# ui_board.net
KiCad netlist of a schematic drawn in EAGLE
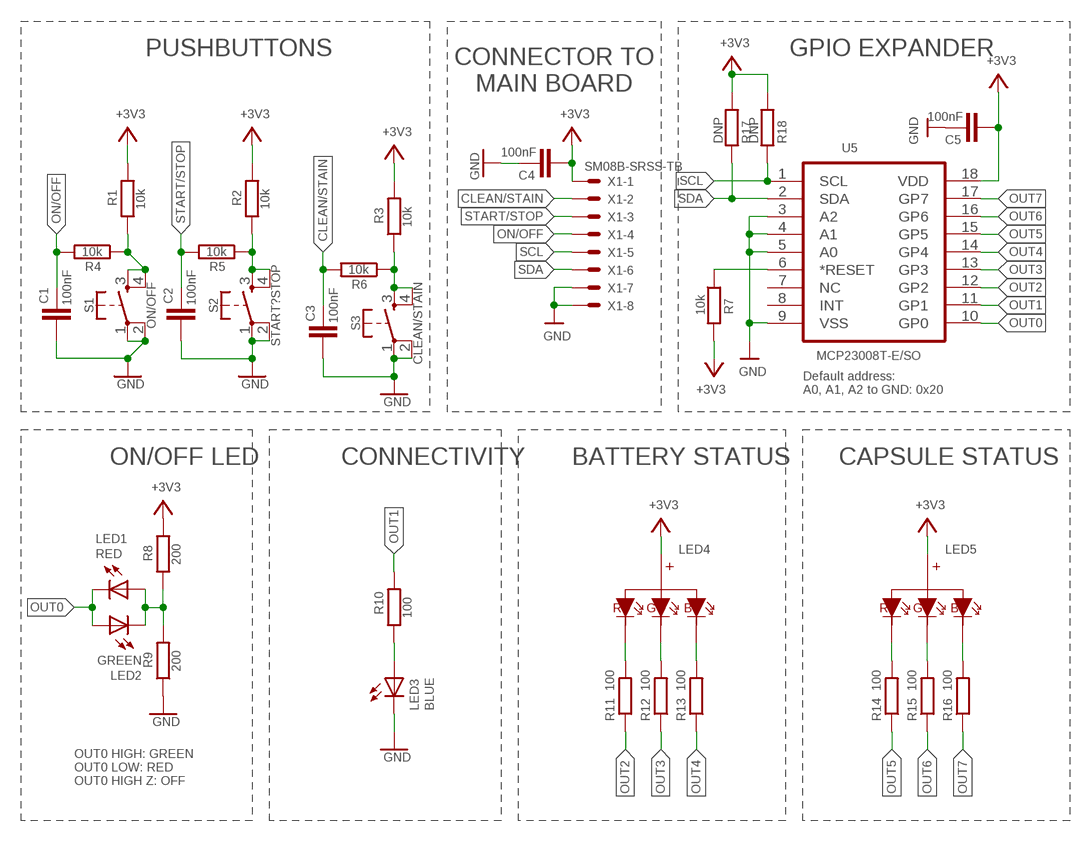
[diagram p0: schematic, sheet 1]

(export (version "E")
  (design (tool "Eeschema 10.0.6"))
  (components
    (comp (ref "C1")
      (value "100nF")
      (footprint "eagle-import:C0402")
      (libsource (lib "eagle-import") (part "C-EUC0402"))
    )
    (comp (ref "C2")
      (value "100nF")
      (footprint "eagle-import:C0402")
      (libsource (lib "eagle-import") (part "C-EUC0402"))
    )
    (comp (ref "C3")
      (value "100nF")
      (footprint "eagle-import:C0402")
      (libsource (lib "eagle-import") (part "C-EUC0402"))
    )
    (comp (ref "C4")
      (value "100nF")
      (footprint "eagle-import:C0402")
      (libsource (lib "eagle-import") (part "C-EUC0402"))
    )
    (comp (ref "C5")
      (value "100nF")
      (footprint "eagle-import:C0402")
      (libsource (lib "eagle-import") (part "C-EUC0402"))
    )
    (comp (ref "LED1")
      (value "RED")
      (footprint "eagle-import:CHIP-LED0603")
      (libsource (lib "eagle-import") (part "LEDCHIP-LED0603"))
    )
    (comp (ref "LED2")
      (value "GREEN")
      (footprint "eagle-import:CHIP-LED0603")
      (libsource (lib "eagle-import") (part "LEDCHIP-LED0603"))
    )
    (comp (ref "LED3")
      (value "BLUE")
      (footprint "eagle-import:CHIP-LED0603")
      (libsource (lib "eagle-import") (part "LEDCHIP-LED0603"))
    )
    (comp (ref "LED4")
      (value "RGB_CAV1")
      (footprint "eagle-import:19-037A_RSGHBHW")
      (libsource (lib "eagle-import") (part "RGB_CAV1"))
    )
    (comp (ref "LED5")
      (value "RGB_CAV1")
      (footprint "eagle-import:19-037A_RSGHBHW")
      (libsource (lib "eagle-import") (part "RGB_CAV1"))
    )
    (comp (ref "R1")
      (value "10k")
      (footprint "eagle-import:R0402")
      (libsource (lib "eagle-import") (part "R-EU_R0402"))
    )
    (comp (ref "R2")
      (value "10k")
      (footprint "eagle-import:R0402")
      (libsource (lib "eagle-import") (part "R-EU_R0402"))
    )
    (comp (ref "R3")
      (value "10k")
      (footprint "eagle-import:R0402")
      (libsource (lib "eagle-import") (part "R-EU_R0402"))
    )
    (comp (ref "R4")
      (value "10k")
      (footprint "eagle-import:R0402")
      (libsource (lib "eagle-import") (part "R-EU_R0402"))
    )
    (comp (ref "R5")
      (value "10k")
      (footprint "eagle-import:R0402")
      (libsource (lib "eagle-import") (part "R-EU_R0402"))
    )
    (comp (ref "R6")
      (value "10k")
      (footprint "eagle-import:R0402")
      (libsource (lib "eagle-import") (part "R-EU_R0402"))
    )
    (comp (ref "R7")
      (value "10k")
      (footprint "eagle-import:R0402")
      (libsource (lib "eagle-import") (part "R-EU_R0402"))
    )
    (comp (ref "R8")
      (value "200")
      (footprint "eagle-import:R0402")
      (libsource (lib "eagle-import") (part "R-EU_R0402"))
    )
    (comp (ref "R9")
      (value "200")
      (footprint "eagle-import:R0402")
      (libsource (lib "eagle-import") (part "R-EU_R0402"))
    )
    (comp (ref "R10")
      (value "100")
      (footprint "eagle-import:R0402")
      (libsource (lib "eagle-import") (part "R-EU_R0402"))
    )
    (comp (ref "R11")
      (value "100")
      (footprint "eagle-import:R0402")
      (libsource (lib "eagle-import") (part "R-EU_R0402"))
    )
    (comp (ref "R12")
      (value "100")
      (footprint "eagle-import:R0402")
      (libsource (lib "eagle-import") (part "R-EU_R0402"))
    )
    (comp (ref "R13")
      (value "100")
      (footprint "eagle-import:R0402")
      (libsource (lib "eagle-import") (part "R-EU_R0402"))
    )
    (comp (ref "R14")
      (value "100")
      (footprint "eagle-import:R0402")
      (libsource (lib "eagle-import") (part "R-EU_R0402"))
    )
    (comp (ref "R15")
      (value "100")
      (footprint "eagle-import:R0402")
      (libsource (lib "eagle-import") (part "R-EU_R0402"))
    )
    (comp (ref "R16")
      (value "100")
      (footprint "eagle-import:R0402")
      (libsource (lib "eagle-import") (part "R-EU_R0402"))
    )
    (comp (ref "R17")
      (value "DNP")
      (footprint "eagle-import:R0402")
      (libsource (lib "eagle-import") (part "R-EU_R0402"))
    )
    (comp (ref "R18")
      (value "DNP")
      (footprint "eagle-import:R0402")
      (libsource (lib "eagle-import") (part "R-EU_R0402"))
    )
    (comp (ref "S1")
      (value "ON/OFF")
      (footprint "eagle-import:TACTILE_SWITCH_SMD_5.2MM")
      (libsource (lib "eagle-import") (part "MOMENTARY-SWITCH-SPST-2-SMD-5.2MM"))
    )
    (comp (ref "S2")
      (value "START?STOP")
      (footprint "eagle-import:TACTILE_SWITCH_SMD_5.2MM")
      (libsource (lib "eagle-import") (part "MOMENTARY-SWITCH-SPST-2-SMD-5.2MM"))
    )
    (comp (ref "S3")
      (value "CLEAN/STAIN")
      (footprint "eagle-import:TACTILE_SWITCH_SMD_5.2MM")
      (libsource (lib "eagle-import") (part "MOMENTARY-SWITCH-SPST-2-SMD-5.2MM"))
    )
    (comp (ref "U5")
      (value "MCP23008T-E/SO")
      (footprint "eagle-import:SOIC127P1030X265-18N")
      (fields (field (name "MF") "Microchip"))
      (libsource (lib "eagle-import") (part "MCP23008T-E/SO"))
    )
    (comp (ref "X1")
      (value "SM08B-SRSS-TB")
      (footprint "eagle-import:SM08B-SRSS-TB")
      (libsource (lib "eagle-import") (part "?M08B-SRSS-TBS"))
    )
  )
  (nets
    (net (code "1") (name "+3V3") (class "Default")
      (node (ref "C4") (pin "2") (pinfunction "2_2") (pintype "passive"))
      (node (ref "C5") (pin "2") (pinfunction "2_2") (pintype "passive"))
      (node (ref "LED4") (pin "A") (pinfunction "A_A") (pintype "bidirectional"))
      (node (ref "LED5") (pin "A") (pinfunction "A_A") (pintype "bidirectional"))
      (node (ref "R1") (pin "2") (pinfunction "2_2") (pintype "passive"))
      (node (ref "R17") (pin "1") (pinfunction "1_1") (pintype "passive"))
      (node (ref "R18") (pin "1") (pinfunction "1_1") (pintype "passive"))
      (node (ref "R2") (pin "2") (pinfunction "2_2") (pintype "passive"))
      (node (ref "R3") (pin "2") (pinfunction "2_2") (pintype "passive"))
      (node (ref "R7") (pin "2") (pinfunction "2_2") (pintype "passive"))
      (node (ref "R8") (pin "2") (pinfunction "2_2") (pintype "passive"))
      (node (ref "U5") (pin "18") (pinfunction "VDD_18") (pintype "power_in"))
      (node (ref "X1") (pin "1") (pinfunction "S_1") (pintype "passive"))
    )
    (net (code "2") (name "CLEAN{slash}STAIN") (class "Default")
      (node (ref "C3") (pin "1") (pinfunction "1_1") (pintype "passive"))
      (node (ref "R6") (pin "2") (pinfunction "2_2") (pintype "passive"))
      (node (ref "X1") (pin "2") (pinfunction "S_2") (pintype "passive"))
    )
    (net (code "3") (name "GND") (class "Default")
      (node (ref "C1") (pin "2") (pinfunction "2_2") (pintype "passive"))
      (node (ref "C2") (pin "2") (pinfunction "2_2") (pintype "passive"))
      (node (ref "C3") (pin "2") (pinfunction "2_2") (pintype "passive"))
      (node (ref "C4") (pin "1") (pinfunction "1_1") (pintype "passive"))
      (node (ref "C5") (pin "1") (pinfunction "1_1") (pintype "passive"))
      (node (ref "LED3") (pin "C") (pinfunction "C_C") (pintype "passive"))
      (node (ref "R9") (pin "1") (pinfunction "1_1") (pintype "passive"))
      (node (ref "S1") (pin "1") (pinfunction "1_1") (pintype "passive"))
      (node (ref "S1") (pin "2") (pinfunction "2_2") (pintype "passive"))
      (node (ref "S2") (pin "1") (pinfunction "1_1") (pintype "passive"))
      (node (ref "S2") (pin "2") (pinfunction "2_2") (pintype "passive"))
      (node (ref "S3") (pin "1") (pinfunction "1_1") (pintype "passive"))
      (node (ref "S3") (pin "2") (pinfunction "2_2") (pintype "passive"))
      (node (ref "U5") (pin "3") (pinfunction "A2_3") (pintype "passive"))
      (node (ref "U5") (pin "4") (pinfunction "A1_4") (pintype "input"))
      (node (ref "U5") (pin "5") (pinfunction "A0_5") (pintype "input"))
      (node (ref "U5") (pin "9") (pinfunction "VSS_9") (pintype "passive"))
      (node (ref "X1") (pin "7") (pinfunction "S_7") (pintype "passive"))
      (node (ref "X1") (pin "8") (pinfunction "S_8") (pintype "passive"))
    )
    (net (code "4") (name "Net-(LED1-PadA)") (class "Default")
      (node (ref "LED1") (pin "A") (pinfunction "A_A") (pintype "passive"))
      (node (ref "LED2") (pin "C") (pinfunction "C_C") (pintype "passive"))
      (node (ref "R8") (pin "1") (pinfunction "1_1") (pintype "passive"))
      (node (ref "R9") (pin "2") (pinfunction "2_2") (pintype "passive"))
    )
    (net (code "5") (name "Net-(LED3-PadA)") (class "Default")
      (node (ref "LED3") (pin "A") (pinfunction "A_A") (pintype "passive"))
      (node (ref "R10") (pin "1") (pinfunction "1_1") (pintype "passive"))
    )
    (net (code "6") (name "Net-(LED4-PadB)") (class "Default")
      (node (ref "LED4") (pin "B") (pinfunction "B_B") (pintype "bidirectional"))
      (node (ref "R13") (pin "2") (pinfunction "2_2") (pintype "passive"))
    )
    (net (code "7") (name "Net-(LED4-PadG)") (class "Default")
      (node (ref "LED4") (pin "G") (pinfunction "G_G") (pintype "bidirectional"))
      (node (ref "R12") (pin "2") (pinfunction "2_2") (pintype "passive"))
    )
    (net (code "8") (name "Net-(LED4-PadR)") (class "Default")
      (node (ref "LED4") (pin "R") (pinfunction "R_R") (pintype "bidirectional"))
      (node (ref "R11") (pin "2") (pinfunction "2_2") (pintype "passive"))
    )
    (net (code "9") (name "Net-(LED5-PadB)") (class "Default")
      (node (ref "LED5") (pin "B") (pinfunction "B_B") (pintype "bidirectional"))
      (node (ref "R16") (pin "2") (pinfunction "2_2") (pintype "passive"))
    )
    (net (code "10") (name "Net-(LED5-PadG)") (class "Default")
      (node (ref "LED5") (pin "G") (pinfunction "G_G") (pintype "bidirectional"))
      (node (ref "R15") (pin "2") (pinfunction "2_2") (pintype "passive"))
    )
    (net (code "11") (name "Net-(LED5-PadR)") (class "Default")
      (node (ref "LED5") (pin "R") (pinfunction "R_R") (pintype "bidirectional"))
      (node (ref "R14") (pin "2") (pinfunction "2_2") (pintype "passive"))
    )
    (net (code "12") (name "Net-(R1-Pad1)") (class "Default")
      (node (ref "R1") (pin "1") (pinfunction "1_1") (pintype "passive"))
      (node (ref "R4") (pin "1") (pinfunction "1_1") (pintype "passive"))
      (node (ref "S1") (pin "3") (pinfunction "3_3") (pintype "passive"))
      (node (ref "S1") (pin "4") (pinfunction "4_4") (pintype "passive"))
    )
    (net (code "13") (name "Net-(R2-Pad1)") (class "Default")
      (node (ref "R2") (pin "1") (pinfunction "1_1") (pintype "passive"))
      (node (ref "R5") (pin "1") (pinfunction "1_1") (pintype "passive"))
      (node (ref "S2") (pin "3") (pinfunction "3_3") (pintype "passive"))
      (node (ref "S2") (pin "4") (pinfunction "4_4") (pintype "passive"))
    )
    (net (code "14") (name "Net-(R3-Pad1)") (class "Default")
      (node (ref "R3") (pin "1") (pinfunction "1_1") (pintype "passive"))
      (node (ref "R6") (pin "1") (pinfunction "1_1") (pintype "passive"))
      (node (ref "S3") (pin "3") (pinfunction "3_3") (pintype "passive"))
      (node (ref "S3") (pin "4") (pinfunction "4_4") (pintype "passive"))
    )
    (net (code "15") (name "Net-(U5-*RESET)") (class "Default")
      (node (ref "R7") (pin "1") (pinfunction "1_1") (pintype "passive"))
      (node (ref "U5") (pin "6") (pinfunction "*RESET_6") (pintype "input"))
    )
    (net (code "16") (name "ON{slash}OFF") (class "Default")
      (node (ref "C1") (pin "1") (pinfunction "1_1") (pintype "passive"))
      (node (ref "R4") (pin "2") (pinfunction "2_2") (pintype "passive"))
      (node (ref "X1") (pin "4") (pinfunction "S_4") (pintype "passive"))
    )
    (net (code "17") (name "OUT0") (class "Default")
      (node (ref "LED1") (pin "C") (pinfunction "C_C") (pintype "passive"))
      (node (ref "LED2") (pin "A") (pinfunction "A_A") (pintype "passive"))
      (node (ref "U5") (pin "10") (pinfunction "GP0_10") (pintype "passive"))
    )
    (net (code "18") (name "OUT1") (class "Default")
      (node (ref "R10") (pin "2") (pinfunction "2_2") (pintype "passive"))
      (node (ref "U5") (pin "11") (pinfunction "GP1_11") (pintype "passive"))
    )
    (net (code "19") (name "OUT2") (class "Default")
      (node (ref "R11") (pin "1") (pinfunction "1_1") (pintype "passive"))
      (node (ref "U5") (pin "12") (pinfunction "GP2_12") (pintype "passive"))
    )
    (net (code "20") (name "OUT3") (class "Default")
      (node (ref "R12") (pin "1") (pinfunction "1_1") (pintype "passive"))
      (node (ref "U5") (pin "13") (pinfunction "GP3_13") (pintype "passive"))
    )
    (net (code "21") (name "OUT4") (class "Default")
      (node (ref "R13") (pin "1") (pinfunction "1_1") (pintype "passive"))
      (node (ref "U5") (pin "14") (pinfunction "GP4_14") (pintype "passive"))
    )
    (net (code "22") (name "OUT5") (class "Default")
      (node (ref "R14") (pin "1") (pinfunction "1_1") (pintype "passive"))
      (node (ref "U5") (pin "15") (pinfunction "GP5_15") (pintype "passive"))
    )
    (net (code "23") (name "OUT6") (class "Default")
      (node (ref "R15") (pin "1") (pinfunction "1_1") (pintype "passive"))
      (node (ref "U5") (pin "16") (pinfunction "GP6_16") (pintype "passive"))
    )
    (net (code "24") (name "OUT7") (class "Default")
      (node (ref "R16") (pin "1") (pinfunction "1_1") (pintype "passive"))
      (node (ref "U5") (pin "17") (pinfunction "GP7_17") (pintype "passive"))
    )
    (net (code "25") (name "SCL") (class "Default")
      (node (ref "R18") (pin "2") (pinfunction "2_2") (pintype "passive"))
      (node (ref "U5") (pin "1") (pinfunction "SCL_1") (pintype "input"))
      (node (ref "X1") (pin "5") (pinfunction "S_5") (pintype "passive"))
    )
    (net (code "26") (name "SDA") (class "Default")
      (node (ref "R17") (pin "2") (pinfunction "2_2") (pintype "passive"))
      (node (ref "U5") (pin "2") (pinfunction "SDA_2") (pintype "passive"))
      (node (ref "X1") (pin "6") (pinfunction "S_6") (pintype "passive"))
    )
    (net (code "27") (name "START{slash}STOP") (class "Default")
      (node (ref "C2") (pin "1") (pinfunction "1_1") (pintype "passive"))
      (node (ref "R5") (pin "2") (pinfunction "2_2") (pintype "passive"))
      (node (ref "X1") (pin "3") (pinfunction "S_3") (pintype "passive"))
    )
    (net (code "28") (name "unconnected-(U5-INT-Pad8)") (class "Default")
      (node (ref "U5") (pin "8") (pinfunction "INT_8") (pintype "output"))
    )
    (net (code "29") (name "unconnected-(U5-NC-Pad7)") (class "Default")
      (node (ref "U5") (pin "7") (pinfunction "NC_7") (pintype "input"))
    )
  )
)
